# gamma.net
KiCad netlist of a schematic drawn in EAGLE
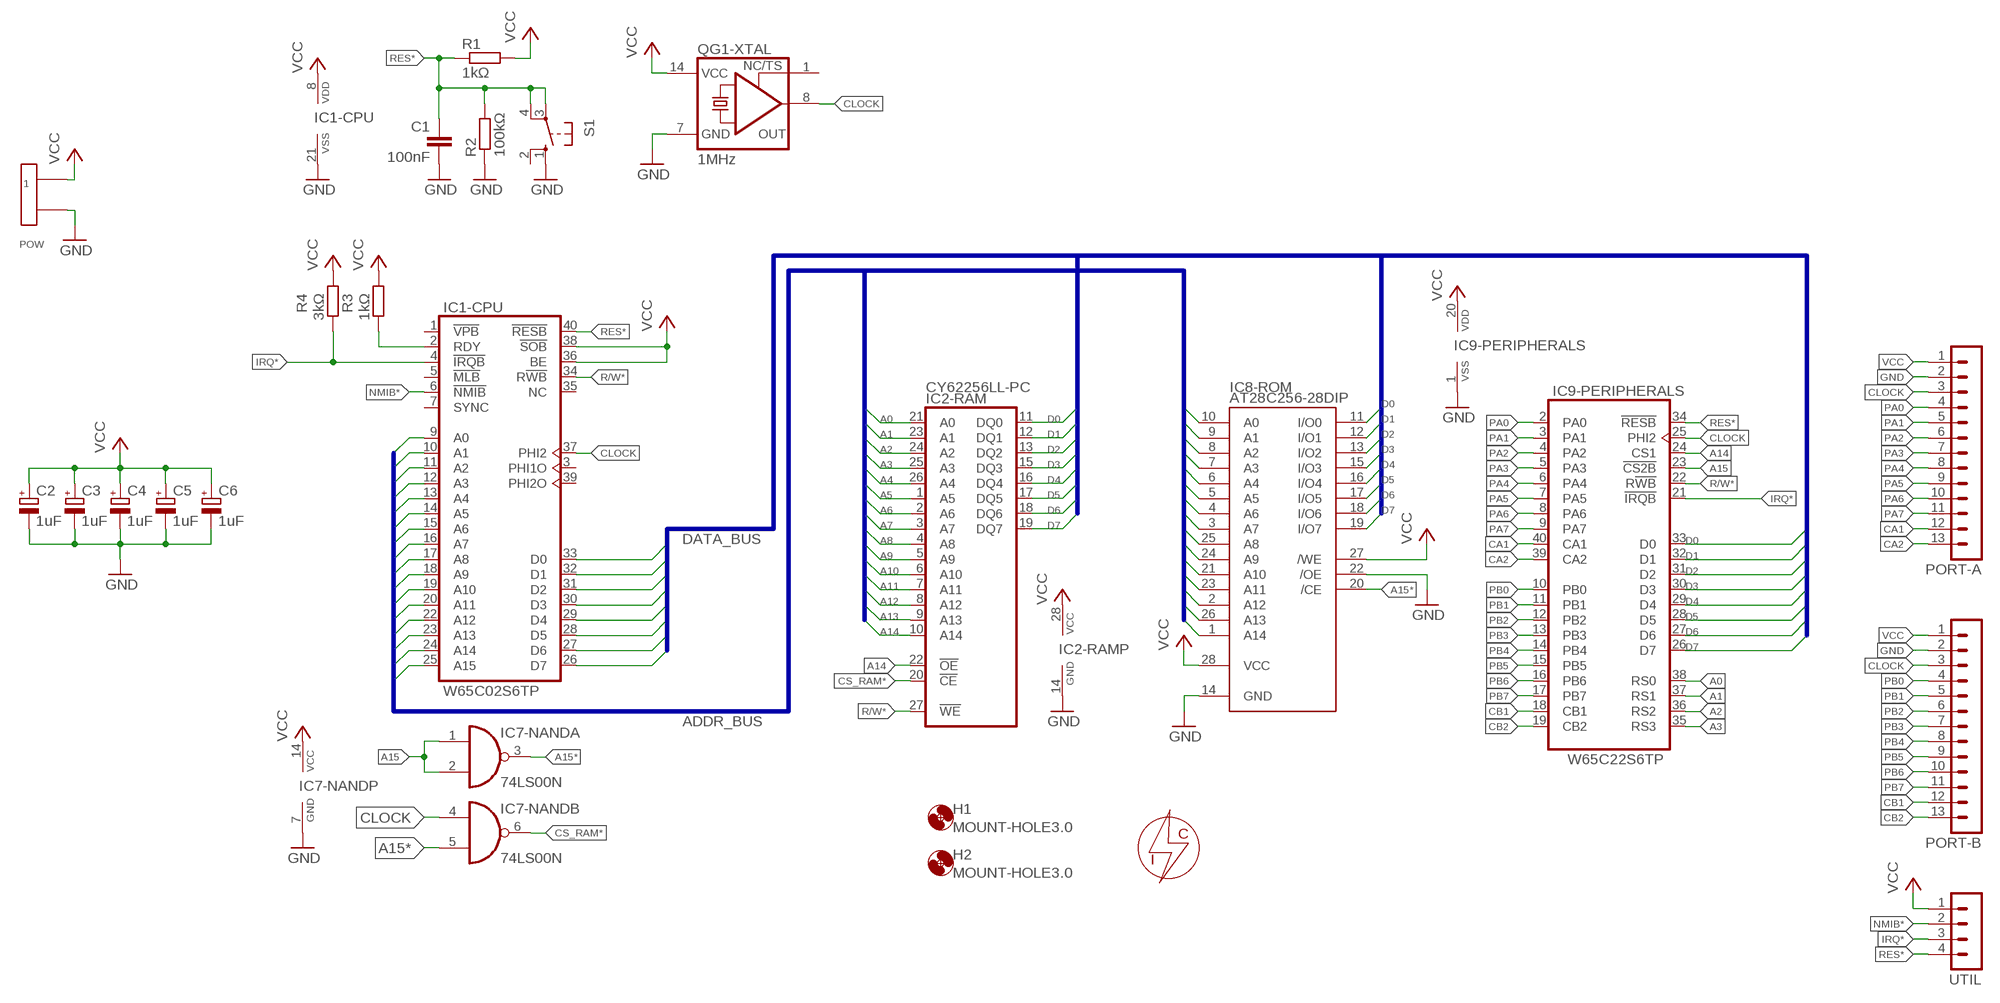
[diagram p0: schematic, sheet 1]

(export (version "E")
  (design (tool "Eeschema 10.0.6"))
  (components
    (comp (ref "C1")
      (value "100nF")
      (footprint "eagle-import:C050-025X075")
      (libsource (lib "eagle-import") (part "C-EU050-025X075"))
    )
    (comp (ref "C2")
      (value "1uF")
      (footprint "eagle-import:E2-5")
      (libsource (lib "eagle-import") (part "CPOL-EUE2-5"))
    )
    (comp (ref "C3")
      (value "1uF")
      (footprint "eagle-import:E2-5")
      (libsource (lib "eagle-import") (part "CPOL-EUE2-5"))
    )
    (comp (ref "C4")
      (value "1uF")
      (footprint "eagle-import:E2-5")
      (libsource (lib "eagle-import") (part "CPOL-EUE2-5"))
    )
    (comp (ref "C5")
      (value "1uF")
      (footprint "eagle-import:E2-5")
      (libsource (lib "eagle-import") (part "CPOL-EUE2-5"))
    )
    (comp (ref "C6")
      (value "1uF")
      (footprint "eagle-import:E2-5")
      (libsource (lib "eagle-import") (part "CPOL-EUE2-5"))
    )
    (comp (ref "H1")
      (value "MOUNT-HOLE3.0")
      (footprint "eagle-import:3,0")
      (libsource (lib "eagle-import") (part "MOUNT-HOLE3.0"))
    )
    (comp (ref "H2")
      (value "MOUNT-HOLE3.0")
      (footprint "eagle-import:3,0")
      (libsource (lib "eagle-import") (part "MOUNT-HOLE3.0"))
    )
    (comp (ref "IC1-CPU")
      (value "W65C02S6TP")
      (footprint "eagle-import:DIL40")
      (libsource (lib "eagle-import") (part "W65C02SP6T"))
    )
    (comp (ref "IC2-RAM")
      (value "CY62256LL-PC")
      (footprint "eagle-import:DIL28-6")
      (libsource (lib "eagle-import") (part "CY62256LL-?PC"))
    )
    (comp (ref "IC7-NAND")
      (value "74LS00N")
      (footprint "eagle-import:DIL14")
      (libsource (lib "eagle-import") (part "7400NLS"))
    )
    (comp (ref "IC8-ROM")
      (value "AT28C256-28DIP")
      (footprint "eagle-import:DIL28-6")
      (libsource (lib "eagle-import") (part "AT28C256-28DIP"))
    )
    (comp (ref "IC9-PERIPHERALS")
      (value "W65C22S6TP")
      (footprint "eagle-import:DIL40")
      (libsource (lib "eagle-import") (part "W65C22SP6T"))
    )
    (comp (ref "PORT-A")
      (value "MA13-1")
      (footprint "eagle-import:MA13-1")
      (libsource (lib "eagle-import") (part "MA13-1"))
    )
    (comp (ref "PORT-B")
      (value "MA13-1")
      (footprint "eagle-import:MA13-1")
      (libsource (lib "eagle-import") (part "MA13-1"))
    )
    (comp (ref "POW")
      (value "AK500")
      (footprint "eagle-import:AK500-2")
      (libsource (lib "eagle-import") (part "AK500"))
    )
    (comp (ref "QG1-XTAL")
      (value "1MHz")
      (footprint "eagle-import:DIL14S")
      (libsource (lib "eagle-import") (part "XO-14"))
    )
    (comp (ref "R1")
      (value "1kΩ")
      (footprint "eagle-import:0207_10")
      (libsource (lib "eagle-import") (part "R-EU_0207/10"))
    )
    (comp (ref "R2")
      (value "100kΩ")
      (footprint "eagle-import:0207_10")
      (libsource (lib "eagle-import") (part "R-EU_0207/10"))
    )
    (comp (ref "R3")
      (value "1kΩ")
      (footprint "eagle-import:0207_10")
      (libsource (lib "eagle-import") (part "R-EU_0207/10"))
    )
    (comp (ref "R4")
      (value "3kΩ")
      (footprint "eagle-import:0207_10")
      (libsource (lib "eagle-import") (part "R-EU_0207/10"))
    )
    (comp (ref "S1")
      (value "10-XX")
      (footprint "eagle-import:B3F-10XX")
      (fields (field (name "MPN") "B3F-1000"))
      (libsource (lib "eagle-import") (part "10-XX"))
    )
    (comp (ref "U$1")
      (value "LOGO-CYBERINDUSTRIES\"")
      (footprint "eagle-import:LOGO-SMALL")
      (libsource (lib "eagle-import") (part "LOGO-CYBERINDUSTRIES{dblquote}"))
    )
    (comp (ref "UTIL")
      (value "MA04-1")
      (footprint "eagle-import:MA04-1")
      (libsource (lib "eagle-import") (part "MA04-1"))
    )
  )
  (nets
    (net (code "1") (name "/A4") (class "Default")
      (node (ref "IC1-CPU") (pin "13") (pinfunction "A4_13") (pintype "output"))
      (node (ref "IC2-RAM") (pin "26") (pinfunction "A4_26") (pintype "input"))
      (node (ref "IC8-ROM") (pin "6") (pinfunction "A4_6") (pintype "bidirectional"))
    )
    (net (code "2") (name "/A5") (class "Default")
      (node (ref "IC1-CPU") (pin "14") (pinfunction "A5_14") (pintype "output"))
      (node (ref "IC2-RAM") (pin "1") (pinfunction "A5_1") (pintype "input"))
      (node (ref "IC8-ROM") (pin "5") (pinfunction "A5_5") (pintype "bidirectional"))
    )
    (net (code "3") (name "/A6") (class "Default")
      (node (ref "IC1-CPU") (pin "15") (pinfunction "A6_15") (pintype "output"))
      (node (ref "IC2-RAM") (pin "2") (pinfunction "A6_2") (pintype "input"))
      (node (ref "IC8-ROM") (pin "4") (pinfunction "A6_4") (pintype "bidirectional"))
    )
    (net (code "4") (name "/A7") (class "Default")
      (node (ref "IC1-CPU") (pin "16") (pinfunction "A7_16") (pintype "output"))
      (node (ref "IC2-RAM") (pin "3") (pinfunction "A7_3") (pintype "input"))
      (node (ref "IC8-ROM") (pin "3") (pinfunction "A7_3") (pintype "bidirectional"))
    )
    (net (code "5") (name "/A8") (class "Default")
      (node (ref "IC1-CPU") (pin "17") (pinfunction "A8_17") (pintype "output"))
      (node (ref "IC2-RAM") (pin "4") (pinfunction "A8_4") (pintype "input"))
      (node (ref "IC8-ROM") (pin "25") (pinfunction "A8_25") (pintype "bidirectional"))
    )
    (net (code "6") (name "/A9") (class "Default")
      (node (ref "IC1-CPU") (pin "18") (pinfunction "A9_18") (pintype "output"))
      (node (ref "IC2-RAM") (pin "5") (pinfunction "A9_5") (pintype "input"))
      (node (ref "IC8-ROM") (pin "24") (pinfunction "A9_24") (pintype "bidirectional"))
    )
    (net (code "7") (name "/A10") (class "Default")
      (node (ref "IC1-CPU") (pin "19") (pinfunction "A10_19") (pintype "output"))
      (node (ref "IC2-RAM") (pin "6") (pinfunction "A10_6") (pintype "input"))
      (node (ref "IC8-ROM") (pin "21") (pinfunction "A10_21") (pintype "bidirectional"))
    )
    (net (code "8") (name "/A11") (class "Default")
      (node (ref "IC1-CPU") (pin "20") (pinfunction "A11_20") (pintype "output"))
      (node (ref "IC2-RAM") (pin "7") (pinfunction "A11_7") (pintype "input"))
      (node (ref "IC8-ROM") (pin "23") (pinfunction "A11_23") (pintype "bidirectional"))
    )
    (net (code "9") (name "/A12") (class "Default")
      (node (ref "IC1-CPU") (pin "22") (pinfunction "A12_22") (pintype "output"))
      (node (ref "IC2-RAM") (pin "8") (pinfunction "A12_8") (pintype "input"))
      (node (ref "IC8-ROM") (pin "2") (pinfunction "A12_2") (pintype "bidirectional"))
    )
    (net (code "10") (name "/A13") (class "Default")
      (node (ref "IC1-CPU") (pin "23") (pinfunction "A13_23") (pintype "output"))
      (node (ref "IC2-RAM") (pin "9") (pinfunction "A13_9") (pintype "input"))
      (node (ref "IC8-ROM") (pin "26") (pinfunction "A13_26") (pintype "bidirectional"))
    )
    (net (code "11") (name "/D0") (class "Default")
      (node (ref "IC1-CPU") (pin "33") (pinfunction "D0_33") (pintype "bidirectional"))
      (node (ref "IC2-RAM") (pin "11") (pinfunction "DQ0_11") (pintype "bidirectional"))
      (node (ref "IC8-ROM") (pin "11") (pinfunction "I/O0_11") (pintype "bidirectional"))
      (node (ref "IC9-PERIPHERALS") (pin "33") (pinfunction "D0_33") (pintype "bidirectional"))
    )
    (net (code "12") (name "/D1") (class "Default")
      (node (ref "IC1-CPU") (pin "32") (pinfunction "D1_32") (pintype "bidirectional"))
      (node (ref "IC2-RAM") (pin "12") (pinfunction "DQ1_12") (pintype "bidirectional"))
      (node (ref "IC8-ROM") (pin "12") (pinfunction "I/O1_12") (pintype "bidirectional"))
      (node (ref "IC9-PERIPHERALS") (pin "32") (pinfunction "D1_32") (pintype "bidirectional"))
    )
    (net (code "13") (name "/D2") (class "Default")
      (node (ref "IC1-CPU") (pin "31") (pinfunction "D2_31") (pintype "bidirectional"))
      (node (ref "IC2-RAM") (pin "13") (pinfunction "DQ2_13") (pintype "bidirectional"))
      (node (ref "IC8-ROM") (pin "13") (pinfunction "I/O2_13") (pintype "bidirectional"))
      (node (ref "IC9-PERIPHERALS") (pin "31") (pinfunction "D2_31") (pintype "bidirectional"))
    )
    (net (code "14") (name "/D3") (class "Default")
      (node (ref "IC1-CPU") (pin "30") (pinfunction "D3_30") (pintype "bidirectional"))
      (node (ref "IC2-RAM") (pin "15") (pinfunction "DQ3_15") (pintype "bidirectional"))
      (node (ref "IC8-ROM") (pin "15") (pinfunction "I/O3_15") (pintype "bidirectional"))
      (node (ref "IC9-PERIPHERALS") (pin "30") (pinfunction "D3_30") (pintype "bidirectional"))
    )
    (net (code "15") (name "/D4") (class "Default")
      (node (ref "IC1-CPU") (pin "29") (pinfunction "D4_29") (pintype "bidirectional"))
      (node (ref "IC2-RAM") (pin "16") (pinfunction "DQ4_16") (pintype "bidirectional"))
      (node (ref "IC8-ROM") (pin "16") (pinfunction "I/O4_16") (pintype "bidirectional"))
      (node (ref "IC9-PERIPHERALS") (pin "29") (pinfunction "D4_29") (pintype "bidirectional"))
    )
    (net (code "16") (name "/D5") (class "Default")
      (node (ref "IC1-CPU") (pin "28") (pinfunction "D5_28") (pintype "bidirectional"))
      (node (ref "IC2-RAM") (pin "17") (pinfunction "DQ5_17") (pintype "bidirectional"))
      (node (ref "IC8-ROM") (pin "17") (pinfunction "I/O5_17") (pintype "bidirectional"))
      (node (ref "IC9-PERIPHERALS") (pin "28") (pinfunction "D5_28") (pintype "bidirectional"))
    )
    (net (code "17") (name "/D6") (class "Default")
      (node (ref "IC1-CPU") (pin "27") (pinfunction "D6_27") (pintype "bidirectional"))
      (node (ref "IC2-RAM") (pin "18") (pinfunction "DQ6_18") (pintype "bidirectional"))
      (node (ref "IC8-ROM") (pin "18") (pinfunction "I/O6_18") (pintype "bidirectional"))
      (node (ref "IC9-PERIPHERALS") (pin "27") (pinfunction "D6_27") (pintype "bidirectional"))
    )
    (net (code "18") (name "/D7") (class "Default")
      (node (ref "IC1-CPU") (pin "26") (pinfunction "D7_26") (pintype "bidirectional"))
      (node (ref "IC2-RAM") (pin "19") (pinfunction "DQ7_19") (pintype "bidirectional"))
      (node (ref "IC8-ROM") (pin "19") (pinfunction "I/O7_19") (pintype "bidirectional"))
      (node (ref "IC9-PERIPHERALS") (pin "26") (pinfunction "D7_26") (pintype "bidirectional"))
    )
    (net (code "19") (name "A0") (class "Default")
      (node (ref "IC1-CPU") (pin "9") (pinfunction "A0_9") (pintype "output"))
      (node (ref "IC2-RAM") (pin "21") (pinfunction "A0_21") (pintype "input"))
      (node (ref "IC8-ROM") (pin "10") (pinfunction "A0_10") (pintype "bidirectional"))
      (node (ref "IC9-PERIPHERALS") (pin "38") (pinfunction "RS0_38") (pintype "input"))
    )
    (net (code "20") (name "A1") (class "Default")
      (node (ref "IC1-CPU") (pin "10") (pinfunction "A1_10") (pintype "output"))
      (node (ref "IC2-RAM") (pin "23") (pinfunction "A1_23") (pintype "input"))
      (node (ref "IC8-ROM") (pin "9") (pinfunction "A1_9") (pintype "bidirectional"))
      (node (ref "IC9-PERIPHERALS") (pin "37") (pinfunction "RS1_37") (pintype "input"))
    )
    (net (code "21") (name "A2") (class "Default")
      (node (ref "IC1-CPU") (pin "11") (pinfunction "A2_11") (pintype "output"))
      (node (ref "IC2-RAM") (pin "24") (pinfunction "A2_24") (pintype "input"))
      (node (ref "IC8-ROM") (pin "8") (pinfunction "A2_8") (pintype "bidirectional"))
      (node (ref "IC9-PERIPHERALS") (pin "36") (pinfunction "RS2_36") (pintype "input"))
    )
    (net (code "22") (name "A3") (class "Default")
      (node (ref "IC1-CPU") (pin "12") (pinfunction "A3_12") (pintype "output"))
      (node (ref "IC2-RAM") (pin "25") (pinfunction "A3_25") (pintype "input"))
      (node (ref "IC8-ROM") (pin "7") (pinfunction "A3_7") (pintype "bidirectional"))
      (node (ref "IC9-PERIPHERALS") (pin "35") (pinfunction "RS3_35") (pintype "input"))
    )
    (net (code "23") (name "A14") (class "Default")
      (node (ref "IC1-CPU") (pin "24") (pinfunction "A14_24") (pintype "output"))
      (node (ref "IC2-RAM") (pin "10") (pinfunction "A14_10") (pintype "input"))
      (node (ref "IC2-RAM") (pin "22") (pinfunction "~{OE}_22") (pintype "input"))
      (node (ref "IC8-ROM") (pin "1") (pinfunction "A14_1") (pintype "bidirectional"))
      (node (ref "IC9-PERIPHERALS") (pin "24") (pinfunction "CS1_24") (pintype "input"))
    )
    (net (code "24") (name "A15") (class "Default")
      (node (ref "IC1-CPU") (pin "25") (pinfunction "A15_25") (pintype "output"))
      (node (ref "IC7-NAND") (pin "1") (pinfunction "I0_1") (pintype "input"))
      (node (ref "IC7-NAND") (pin "2") (pinfunction "I1_2") (pintype "input"))
      (node (ref "IC9-PERIPHERALS") (pin "23") (pinfunction "~{CS2B}_23") (pintype "input"))
    )
    (net (code "25") (name "A15*") (class "Default")
      (node (ref "IC7-NAND") (pin "3") (pinfunction "O_3") (pintype "output"))
      (node (ref "IC7-NAND") (pin "5") (pinfunction "I1_5") (pintype "input"))
      (node (ref "IC8-ROM") (pin "20") (pinfunction "/CE_20") (pintype "bidirectional"))
    )
    (net (code "26") (name "CA1") (class "Default")
      (node (ref "IC9-PERIPHERALS") (pin "40") (pinfunction "CA1_40") (pintype "bidirectional"))
      (node (ref "PORT-A") (pin "12") (pinfunction "12_12") (pintype "passive"))
    )
    (net (code "27") (name "CA2") (class "Default")
      (node (ref "IC9-PERIPHERALS") (pin "39") (pinfunction "CA2_39") (pintype "bidirectional"))
      (node (ref "PORT-A") (pin "13") (pinfunction "13_13") (pintype "passive"))
    )
    (net (code "28") (name "CB1") (class "Default")
      (node (ref "IC9-PERIPHERALS") (pin "18") (pinfunction "CB1_18") (pintype "bidirectional"))
      (node (ref "PORT-B") (pin "12") (pinfunction "12_12") (pintype "passive"))
    )
    (net (code "29") (name "CB2") (class "Default")
      (node (ref "IC9-PERIPHERALS") (pin "19") (pinfunction "CB2_19") (pintype "bidirectional"))
      (node (ref "PORT-B") (pin "13") (pinfunction "13_13") (pintype "passive"))
    )
    (net (code "30") (name "CLOCK") (class "Default")
      (node (ref "IC1-CPU") (pin "37") (pinfunction "PHI2_37") (pintype "input"))
      (node (ref "IC7-NAND") (pin "4") (pinfunction "I0_4") (pintype "input"))
      (node (ref "IC9-PERIPHERALS") (pin "25") (pinfunction "PHI2_25") (pintype "input"))
      (node (ref "PORT-A") (pin "3") (pinfunction "3_3") (pintype "passive"))
      (node (ref "PORT-B") (pin "3") (pinfunction "3_3") (pintype "passive"))
      (node (ref "QG1-XTAL") (pin "8") (pinfunction "OUT_8") (pintype "output"))
    )
    (net (code "31") (name "CS_RAM*") (class "Default")
      (node (ref "IC2-RAM") (pin "20") (pinfunction "~{CE}_20") (pintype "input"))
      (node (ref "IC7-NAND") (pin "6") (pinfunction "O_6") (pintype "output"))
    )
    (net (code "32") (name "GND") (class "Default")
      (node (ref "C1") (pin "2") (pinfunction "2_2") (pintype "passive"))
      (node (ref "C2") (pin "-") (pinfunction "-_-") (pintype "passive"))
      (node (ref "C3") (pin "-") (pinfunction "-_-") (pintype "passive"))
      (node (ref "C4") (pin "-") (pinfunction "-_-") (pintype "passive"))
      (node (ref "C5") (pin "-") (pinfunction "-_-") (pintype "passive"))
      (node (ref "C6") (pin "-") (pinfunction "-_-") (pintype "passive"))
      (node (ref "IC1-CPU") (pin "21") (pinfunction "VSS_21") (pintype "power_in"))
      (node (ref "IC2-RAM") (pin "14") (pinfunction "GND_14") (pintype "power_in"))
      (node (ref "IC7-NAND") (pin "7") (pinfunction "GND_7") (pintype "power_in"))
      (node (ref "IC8-ROM") (pin "14") (pinfunction "GND_14") (pintype "bidirectional"))
      (node (ref "IC8-ROM") (pin "22") (pinfunction "/OE_22") (pintype "bidirectional"))
      (node (ref "IC9-PERIPHERALS") (pin "1") (pinfunction "VSS_1") (pintype "power_in"))
      (node (ref "PORT-A") (pin "2") (pinfunction "2_2") (pintype "passive"))
      (node (ref "PORT-B") (pin "2") (pinfunction "2_2") (pintype "passive"))
      (node (ref "POW") (pin "P$2") (pinfunction "P$2_P$2") (pintype "bidirectional"))
      (node (ref "QG1-XTAL") (pin "7") (pinfunction "GND_7") (pintype "power_in"))
      (node (ref "R2") (pin "1") (pinfunction "1_1") (pintype "passive"))
      (node (ref "S1") (pin "1") (pinfunction "S_1") (pintype "passive"))
    )
    (net (code "33") (name "IRQ*") (class "Default")
      (node (ref "IC1-CPU") (pin "4") (pinfunction "~{IRQB}_4") (pintype "input"))
      (node (ref "IC9-PERIPHERALS") (pin "21") (pinfunction "~{IRQB}_21") (pintype "output"))
      (node (ref "R4") (pin "2") (pinfunction "2_2") (pintype "passive"))
      (node (ref "UTIL") (pin "3") (pinfunction "3_3") (pintype "passive"))
    )
    (net (code "34") (name "NMIB*") (class "Default")
      (node (ref "IC1-CPU") (pin "6") (pinfunction "~{NMIB}_6") (pintype "input"))
      (node (ref "UTIL") (pin "2") (pinfunction "2_2") (pintype "passive"))
    )
    (net (code "35") (name "Net-(IC1-CPUA-RDY)") (class "Default")
      (node (ref "IC1-CPU") (pin "2") (pinfunction "RDY_2") (pintype "input"))
      (node (ref "R3") (pin "2") (pinfunction "2_2") (pintype "passive"))
    )
    (net (code "36") (name "PA0") (class "Default")
      (node (ref "IC9-PERIPHERALS") (pin "2") (pinfunction "PA0_2") (pintype "bidirectional"))
      (node (ref "PORT-A") (pin "4") (pinfunction "4_4") (pintype "passive"))
    )
    (net (code "37") (name "PA1") (class "Default")
      (node (ref "IC9-PERIPHERALS") (pin "3") (pinfunction "PA1_3") (pintype "bidirectional"))
      (node (ref "PORT-A") (pin "5") (pinfunction "5_5") (pintype "passive"))
    )
    (net (code "38") (name "PA2") (class "Default")
      (node (ref "IC9-PERIPHERALS") (pin "4") (pinfunction "PA2_4") (pintype "bidirectional"))
      (node (ref "PORT-A") (pin "6") (pinfunction "6_6") (pintype "passive"))
    )
    (net (code "39") (name "PA3") (class "Default")
      (node (ref "IC9-PERIPHERALS") (pin "5") (pinfunction "PA3_5") (pintype "bidirectional"))
      (node (ref "PORT-A") (pin "7") (pinfunction "7_7") (pintype "passive"))
    )
    (net (code "40") (name "PA4") (class "Default")
      (node (ref "IC9-PERIPHERALS") (pin "6") (pinfunction "PA4_6") (pintype "bidirectional"))
      (node (ref "PORT-A") (pin "8") (pinfunction "8_8") (pintype "passive"))
    )
    (net (code "41") (name "PA5") (class "Default")
      (node (ref "IC9-PERIPHERALS") (pin "7") (pinfunction "PA5_7") (pintype "bidirectional"))
      (node (ref "PORT-A") (pin "9") (pinfunction "9_9") (pintype "passive"))
    )
    (net (code "42") (name "PA6") (class "Default")
      (node (ref "IC9-PERIPHERALS") (pin "8") (pinfunction "PA6_8") (pintype "bidirectional"))
      (node (ref "PORT-A") (pin "10") (pinfunction "10_10") (pintype "passive"))
    )
    (net (code "43") (name "PA7") (class "Default")
      (node (ref "IC9-PERIPHERALS") (pin "9") (pinfunction "PA7_9") (pintype "bidirectional"))
      (node (ref "PORT-A") (pin "11") (pinfunction "11_11") (pintype "passive"))
    )
    (net (code "44") (name "PB0") (class "Default")
      (node (ref "IC9-PERIPHERALS") (pin "10") (pinfunction "PB0_10") (pintype "bidirectional"))
      (node (ref "PORT-B") (pin "4") (pinfunction "4_4") (pintype "passive"))
    )
    (net (code "45") (name "PB1") (class "Default")
      (node (ref "IC9-PERIPHERALS") (pin "11") (pinfunction "PB1_11") (pintype "bidirectional"))
      (node (ref "PORT-B") (pin "5") (pinfunction "5_5") (pintype "passive"))
    )
    (net (code "46") (name "PB2") (class "Default")
      (node (ref "IC9-PERIPHERALS") (pin "12") (pinfunction "PB2_12") (pintype "bidirectional"))
      (node (ref "PORT-B") (pin "6") (pinfunction "6_6") (pintype "passive"))
    )
    (net (code "47") (name "PB3") (class "Default")
      (node (ref "IC9-PERIPHERALS") (pin "13") (pinfunction "PB3_13") (pintype "bidirectional"))
      (node (ref "PORT-B") (pin "7") (pinfunction "7_7") (pintype "passive"))
    )
    (net (code "48") (name "PB4") (class "Default")
      (node (ref "IC9-PERIPHERALS") (pin "14") (pinfunction "PB4_14") (pintype "bidirectional"))
      (node (ref "PORT-B") (pin "8") (pinfunction "8_8") (pintype "passive"))
    )
    (net (code "49") (name "PB5") (class "Default")
      (node (ref "IC9-PERIPHERALS") (pin "15") (pinfunction "PB5_15") (pintype "bidirectional"))
      (node (ref "PORT-B") (pin "9") (pinfunction "9_9") (pintype "passive"))
    )
    (net (code "50") (name "PB6") (class "Default")
      (node (ref "IC9-PERIPHERALS") (pin "16") (pinfunction "PB6_16") (pintype "bidirectional"))
      (node (ref "PORT-B") (pin "10") (pinfunction "10_10") (pintype "passive"))
    )
    (net (code "51") (name "PB7") (class "Default")
      (node (ref "IC9-PERIPHERALS") (pin "17") (pinfunction "PB7_17") (pintype "bidirectional"))
      (node (ref "PORT-B") (pin "11") (pinfunction "11_11") (pintype "passive"))
    )
    (net (code "52") (name "RES*") (class "Default")
      (node (ref "C1") (pin "1") (pinfunction "1_1") (pintype "passive"))
      (node (ref "IC1-CPU") (pin "40") (pinfunction "~{RESB}_40") (pintype "input"))
      (node (ref "IC9-PERIPHERALS") (pin "34") (pinfunction "~{RESB}_34") (pintype "input"))
      (node (ref "R1") (pin "1") (pinfunction "1_1") (pintype "passive"))
      (node (ref "R2") (pin "2") (pinfunction "2_2") (pintype "passive"))
      (node (ref "S1") (pin "3") (pinfunction "P_3") (pintype "passive"))
      (node (ref "S1") (pin "4") (pinfunction "P1_4") (pintype "passive"))
      (node (ref "UTIL") (pin "4") (pinfunction "4_4") (pintype "passive"))
    )
    (net (code "53") (name "R{slash}W*") (class "Default")
      (node (ref "IC1-CPU") (pin "34") (pinfunction "R~{WB}_34") (pintype "output"))
      (node (ref "IC2-RAM") (pin "27") (pinfunction "~{WE}_27") (pintype "input"))
      (node (ref "IC9-PERIPHERALS") (pin "22") (pinfunction "R~{WB}_22") (pintype "input"))
    )
    (net (code "54") (name "VCC") (class "Default")
      (node (ref "C2") (pin "+") (pinfunction "+_+") (pintype "passive"))
      (node (ref "C3") (pin "+") (pinfunction "+_+") (pintype "passive"))
      (node (ref "C4") (pin "+") (pinfunction "+_+") (pintype "passive"))
      (node (ref "C5") (pin "+") (pinfunction "+_+") (pintype "passive"))
      (node (ref "C6") (pin "+") (pinfunction "+_+") (pintype "passive"))
      (node (ref "IC1-CPU") (pin "36") (pinfunction "BE_36") (pintype "input"))
      (node (ref "IC1-CPU") (pin "38") (pinfunction "~{SOB}_38") (pintype "input"))
      (node (ref "IC1-CPU") (pin "8") (pinfunction "VDD_8") (pintype "power_in"))
      (node (ref "IC2-RAM") (pin "28") (pinfunction "VCC_28") (pintype "power_in"))
      (node (ref "IC7-NAND") (pin "14") (pinfunction "VCC_14") (pintype "power_in"))
      (node (ref "IC8-ROM") (pin "27") (pinfunction "/WE_27") (pintype "bidirectional"))
      (node (ref "IC8-ROM") (pin "28") (pinfunction "VCC_28") (pintype "bidirectional"))
      (node (ref "IC9-PERIPHERALS") (pin "20") (pinfunction "VDD_20") (pintype "power_in"))
      (node (ref "PORT-A") (pin "1") (pinfunction "1_1") (pintype "passive"))
      (node (ref "PORT-B") (pin "1") (pinfunction "1_1") (pintype "passive"))
      (node (ref "POW") (pin "P$1") (pinfunction "P$1_P$1") (pintype "bidirectional"))
      (node (ref "QG1-XTAL") (pin "14") (pinfunction "VCC_14") (pintype "power_in"))
      (node (ref "R1") (pin "2") (pinfunction "2_2") (pintype "passive"))
      (node (ref "R3") (pin "1") (pinfunction "1_1") (pintype "passive"))
      (node (ref "R4") (pin "1") (pinfunction "1_1") (pintype "passive"))
      (node (ref "UTIL") (pin "1") (pinfunction "1_1") (pintype "passive"))
    )
    (net (code "55") (name "unconnected-(IC1-CPUA-NC-Pad35)") (class "Default")
      (node (ref "IC1-CPU") (pin "35") (pinfunction "NC_35") (pintype "no_connect"))
    )
    (net (code "56") (name "unconnected-(IC1-CPUA-PHI1O-Pad3)") (class "Default")
      (node (ref "IC1-CPU") (pin "3") (pinfunction "PHI1O_3") (pintype "output"))
    )
    (net (code "57") (name "unconnected-(IC1-CPUA-PHI2O-Pad39)") (class "Default")
      (node (ref "IC1-CPU") (pin "39") (pinfunction "PHI2O_39") (pintype "output"))
    )
    (net (code "58") (name "unconnected-(IC1-CPUA-SYNC-Pad7)") (class "Default")
      (node (ref "IC1-CPU") (pin "7") (pinfunction "SYNC_7") (pintype "output"))
    )
    (net (code "59") (name "unconnected-(IC1-CPUA-~{MLB}-Pad5)") (class "Default")
      (node (ref "IC1-CPU") (pin "5") (pinfunction "~{MLB}_5") (pintype "output"))
    )
    (net (code "60") (name "unconnected-(IC1-CPUA-~{VPB}-Pad1)") (class "Default")
      (node (ref "IC1-CPU") (pin "1") (pinfunction "~{VPB}_1") (pintype "output"))
    )
    (net (code "61") (name "unconnected-(QG1-XTAL-TS-Pad1)") (class "Default")
      (node (ref "QG1-XTAL") (pin "1") (pinfunction "TS_1") (pintype "passive"))
    )
    (net (code "62") (name "unconnected-(S1-S1-Pad2)") (class "Default")
      (node (ref "S1") (pin "2") (pinfunction "S1_2") (pintype "passive"))
    )
  )
)
